# Power.net
KiCad netlist of a schematic drawn in Altium Designer
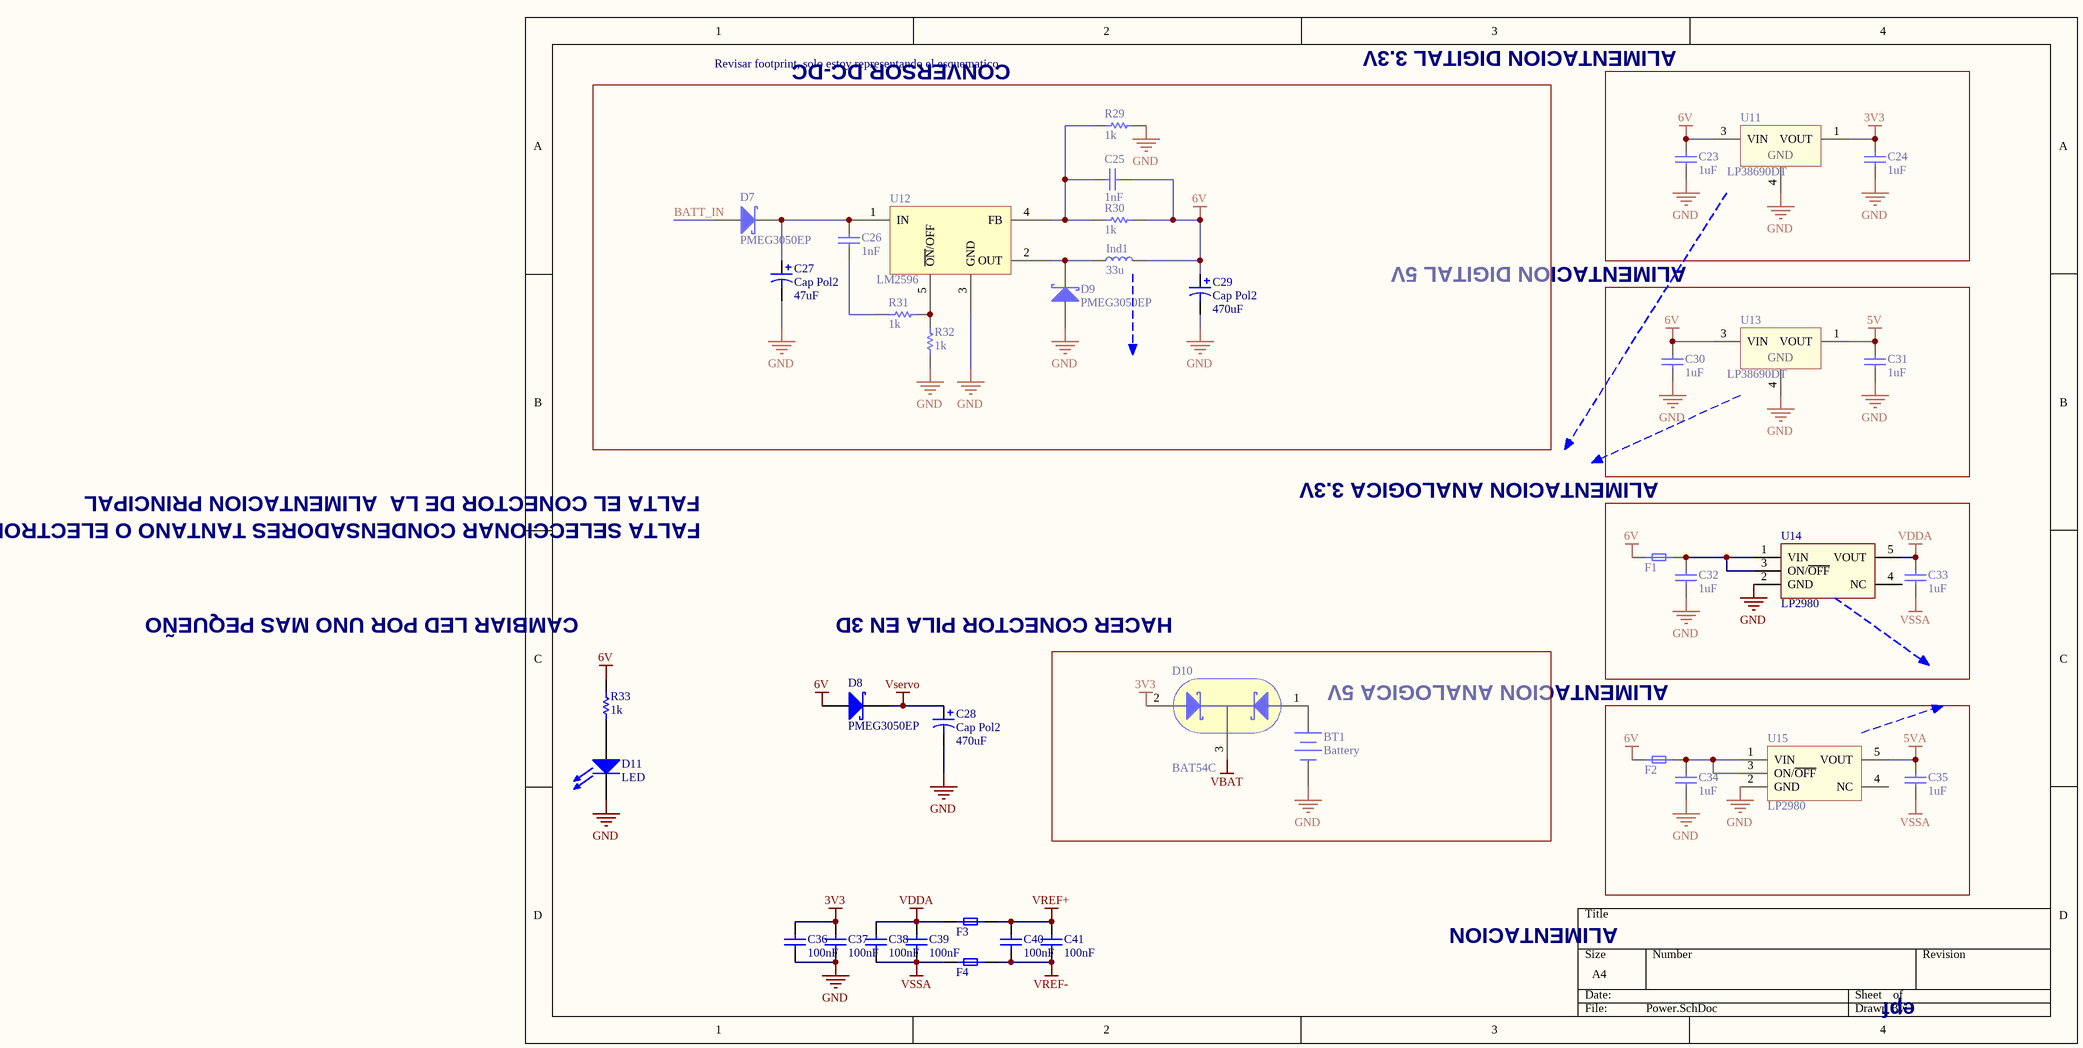
[diagram p0: Power.SchDoc]

(export (version "E")
  (design (tool "Eeschema 10.0.6"))
  (components
    (comp (ref "BT1")
      (value "Battery")
      (footprint "BC501SM")
      (description "Multicell Battery")
      (fields (field (name "PUBLISHER") "Altium Limited"))
      (libsource (lib "epf") (part "Battery"))
    )
    (comp (ref "C23")
      (value "1uF")
      (footprint "0805_CAP")
      (fields (field (name "Comment") "Capacitor"))
      (libsource (lib "epf") (part "Cap"))
    )
    (comp (ref "C24")
      (value "1uF")
      (footprint "0805_CAP")
      (fields (field (name "Comment") "Capacitor"))
      (libsource (lib "epf") (part "Cap"))
    )
    (comp (ref "C25")
      (value "1nF")
      (footprint "0805_CAP")
      (fields (field (name "Comment") "Capacitor"))
      (libsource (lib "epf") (part "Cap"))
    )
    (comp (ref "C26")
      (value "1nF")
      (footprint "0805_CAP")
      (fields (field (name "Comment") "Capacitor"))
      (libsource (lib "epf") (part "Cap"))
    )
    (comp (ref "C27")
      (value "Cap Pol2")
      (footprint "TC7360-2924")
      (description "Polarized Capacitor (Axial)")
      (fields (field (name "ALTIUM_VALUE") "47uF") (field (name "PUBLISHER") "Altium Limited"))
      (libsource (lib "epf") (part "Cap Pol2"))
    )
    (comp (ref "C28")
      (value "Cap Pol2")
      (footprint "TC7360-2924")
      (description "Polarized Capacitor (Axial)")
      (fields (field (name "ALTIUM_VALUE") "470uF") (field (name "PUBLISHER") "Altium Limited"))
      (libsource (lib "epf") (part "Cap Pol2"))
    )
    (comp (ref "C29")
      (value "Cap Pol2")
      (footprint "TC7360-2924")
      (description "Polarized Capacitor (Axial)")
      (fields (field (name "ALTIUM_VALUE") "470uF") (field (name "PUBLISHER") "Altium Limited"))
      (libsource (lib "epf") (part "Cap Pol2"))
    )
    (comp (ref "C30")
      (value "1uF")
      (footprint "0805_CAP")
      (fields (field (name "Comment") "Capacitor"))
      (libsource (lib "epf") (part "Cap"))
    )
    (comp (ref "C31")
      (value "1uF")
      (footprint "0805_CAP")
      (fields (field (name "Comment") "Capacitor"))
      (libsource (lib "epf") (part "Cap"))
    )
    (comp (ref "C32")
      (value "1uF")
      (footprint "CAP0402")
      (fields (field (name "Comment") "Capacitor"))
      (libsource (lib "epf") (part "Cap"))
    )
    (comp (ref "C33")
      (value "1uF")
      (footprint "CAP0402")
      (fields (field (name "Comment") "Capacitor"))
      (libsource (lib "epf") (part "Cap"))
    )
    (comp (ref "C34")
      (value "1uF")
      (footprint "CAP0402")
      (fields (field (name "Comment") "Capacitor"))
      (libsource (lib "epf") (part "Cap"))
    )
    (comp (ref "C35")
      (value "1uF")
      (footprint "CAP0402")
      (fields (field (name "Comment") "Capacitor"))
      (libsource (lib "epf") (part "Cap"))
    )
    (comp (ref "C36")
      (value "100nF")
      (footprint "CAP0402")
      (fields (field (name "Comment") "Capacitor"))
      (libsource (lib "epf") (part "Cap"))
    )
    (comp (ref "C37")
      (value "100nF")
      (footprint "CAP0402")
      (fields (field (name "Comment") "Capacitor"))
      (libsource (lib "epf") (part "Cap"))
    )
    (comp (ref "C38")
      (value "100nF")
      (footprint "CAP0402")
      (fields (field (name "Comment") "Capacitor"))
      (libsource (lib "epf") (part "Cap"))
    )
    (comp (ref "C39")
      (value "100nF")
      (footprint "CAP0402")
      (fields (field (name "Comment") "Capacitor"))
      (libsource (lib "epf") (part "Cap"))
    )
    (comp (ref "C40")
      (value "100nF")
      (footprint "CAP0402")
      (fields (field (name "Comment") "Capacitor"))
      (libsource (lib "epf") (part "Cap"))
    )
    (comp (ref "C41")
      (value "100nF")
      (footprint "CAP0402")
      (fields (field (name "Comment") "Capacitor"))
      (libsource (lib "epf") (part "Cap"))
    )
    (comp (ref "D7")
      (value "PMEG3050EP")
      (footprint "SOD128")
      (description "DIODO 5A DC-DC")
      (libsource (lib "epf") (part "PMEG3050EP"))
    )
    (comp (ref "D8")
      (value "PMEG3050EP")
      (footprint "SOD128")
      (description "DIODO 5A DC-DC")
      (libsource (lib "epf") (part "PMEG3050EP"))
    )
    (comp (ref "D9")
      (value "PMEG3050EP")
      (footprint "SOD128")
      (description "DIODO 5A DC-DC")
      (libsource (lib "epf") (part "PMEG3050EP"))
    )
    (comp (ref "D10")
      (value "BAT54C")
      (footprint "SOT23")
      (description "Single schottky")
      (libsource (lib "epf") (part "BAT54C"))
    )
    (comp (ref "D11") (value "LED") (footprint "PLCC-2Rojo") (libsource (lib "epf") (part "LED1")))
    (comp (ref "F1") (value "Ferrita") (footprint "IND0603") (libsource (lib "epf") (part "Ferrita")))
    (comp (ref "F2") (value "Ferrita") (footprint "IND0603") (libsource (lib "epf") (part "Ferrita")))
    (comp (ref "F3") (value "Ferrita") (footprint "IND0603") (libsource (lib "epf") (part "Ferrita")))
    (comp (ref "F4") (value "Ferrita") (footprint "IND0603") (libsource (lib "epf") (part "Ferrita")))
    (comp (ref "Ind1")
      (value "Ind2")
      (footprint "CDRH127")
      (fields (field (name "VALOR") "33u"))
      (libsource (lib "epf") (part "Ind2"))
    )
    (comp (ref "R29")
      (value "1k")
      (footprint "0805_RES")
      (fields (field (name "Comment") "Resistor"))
      (libsource (lib "epf") (part "Res"))
    )
    (comp (ref "R30")
      (value "1k")
      (footprint "0805_RES")
      (fields (field (name "Comment") "Resistor"))
      (libsource (lib "epf") (part "Res"))
    )
    (comp (ref "R31")
      (value "1k")
      (footprint "0805_RES")
      (fields (field (name "Comment") "Resistor"))
      (libsource (lib "epf") (part "Res"))
    )
    (comp (ref "R32")
      (value "1k")
      (footprint "0805_RES")
      (fields (field (name "Comment") "Resistor"))
      (libsource (lib "epf") (part "Res"))
    )
    (comp (ref "R33")
      (value "1k")
      (footprint "RES0402")
      (fields (field (name "Comment") "Resistor"))
      (libsource (lib "epf") (part "Res"))
    )
    (comp (ref "U11")
      (value "LP38690DT")
      (footprint "TO252-3N")
      (description "Current 1A")
      (libsource (lib "epf") (part "LP38690DT"))
    )
    (comp (ref "U12") (value "LM2596") (footprint "TO-263 - LM2596") (libsource (lib "epf") (part "LM2596")))
    (comp (ref "U13")
      (value "LP38690DT")
      (footprint "TO252-3N")
      (description "Current 1A")
      (libsource (lib "epf") (part "LP38690DT"))
    )
    (comp (ref "U14")
      (value "LP2980")
      (footprint "SOT23-5BN")
      (description "Current 50mA")
      (libsource (lib "epf") (part "LP2980"))
    )
    (comp (ref "U15")
      (value "LP2980")
      (footprint "SOT23-5BN")
      (description "Current 50mA")
      (libsource (lib "epf") (part "LP2980"))
    )
  )
  (nets
    (net (code "1") (name "/BATT_IN") (class "Default")
      (node (ref "D7") (pin "2") (pinfunction "A_2") (pintype "passive"))
    )
    (net (code "2") (name "3V3") (class "Default")
      (node (ref "C24") (pin "2") (pinfunction "2_2") (pintype "passive"))
      (node (ref "C36") (pin "2") (pinfunction "2_2") (pintype "passive"))
      (node (ref "C37") (pin "2") (pinfunction "2_2") (pintype "passive"))
      (node (ref "D10") (pin "2") (pinfunction "NC_2") (pintype "passive"))
      (node (ref "U11") (pin "1") (pinfunction "VOUT_1") (pintype "passive"))
    )
    (net (code "3") (name "5V") (class "Default")
      (node (ref "C31") (pin "2") (pinfunction "2_2") (pintype "passive"))
      (node (ref "U13") (pin "1") (pinfunction "VOUT_1") (pintype "passive"))
    )
    (net (code "4") (name "5VA") (class "Default")
      (node (ref "C35") (pin "2") (pinfunction "2_2") (pintype "passive"))
      (node (ref "U15") (pin "5") (pinfunction "VOUT_5") (pintype "passive"))
    )
    (net (code "5") (name "6V") (class "Default")
      (node (ref "C23") (pin "2") (pinfunction "2_2") (pintype "passive"))
      (node (ref "C25") (pin "1") (pinfunction "1_1") (pintype "passive"))
      (node (ref "C29") (pin "1") (pinfunction "1_1") (pintype "passive"))
      (node (ref "C30") (pin "2") (pinfunction "2_2") (pintype "passive"))
      (node (ref "D8") (pin "2") (pinfunction "A_2") (pintype "passive"))
      (node (ref "F1") (pin "1") (pinfunction "1_1") (pintype "passive"))
      (node (ref "F2") (pin "1") (pinfunction "1_1") (pintype "passive"))
      (node (ref "Ind1") (pin "2") (pinfunction "2_2") (pintype "passive"))
      (node (ref "R30") (pin "2") (pinfunction "2_2") (pintype "passive"))
      (node (ref "R33") (pin "1") (pinfunction "1_1") (pintype "passive"))
      (node (ref "U11") (pin "3") (pinfunction "VIN_3") (pintype "passive"))
      (node (ref "U13") (pin "3") (pinfunction "VIN_3") (pintype "passive"))
    )
    (net (code "6") (name "GND") (class "Default")
      (node (ref "BT1") (pin "2") (pinfunction "-_2") (pintype "passive"))
      (node (ref "C23") (pin "1") (pinfunction "1_1") (pintype "passive"))
      (node (ref "C24") (pin "1") (pinfunction "1_1") (pintype "passive"))
      (node (ref "C27") (pin "2") (pinfunction "2_2") (pintype "passive"))
      (node (ref "C28") (pin "2") (pinfunction "2_2") (pintype "passive"))
      (node (ref "C29") (pin "2") (pinfunction "2_2") (pintype "passive"))
      (node (ref "C30") (pin "1") (pinfunction "1_1") (pintype "passive"))
      (node (ref "C31") (pin "1") (pinfunction "1_1") (pintype "passive"))
      (node (ref "C32") (pin "1") (pinfunction "1_1") (pintype "passive"))
      (node (ref "C34") (pin "1") (pinfunction "1_1") (pintype "passive"))
      (node (ref "C36") (pin "1") (pinfunction "1_1") (pintype "passive"))
      (node (ref "C37") (pin "1") (pinfunction "1_1") (pintype "passive"))
      (node (ref "D11") (pin "2") (pinfunction "K_2") (pintype "passive"))
      (node (ref "D9") (pin "2") (pinfunction "A_2") (pintype "passive"))
      (node (ref "R29") (pin "2") (pinfunction "2_2") (pintype "passive"))
      (node (ref "R32") (pin "1") (pinfunction "1_1") (pintype "passive"))
      (node (ref "U11") (pin "4") (pinfunction "GND_4") (pintype "passive"))
      (node (ref "U12") (pin "3") (pinfunction "GND_3") (pintype "passive"))
      (node (ref "U13") (pin "4") (pinfunction "GND_4") (pintype "passive"))
      (node (ref "U14") (pin "2") (pinfunction "GND_2") (pintype "passive"))
      (node (ref "U15") (pin "2") (pinfunction "GND_2") (pintype "passive"))
    )
    (net (code "7") (name "Net-(BT1-+)") (class "Default")
      (node (ref "BT1") (pin "1") (pinfunction "+_1") (pintype "passive"))
      (node (ref "D10") (pin "1") (pinfunction "A_1") (pintype "passive"))
    )
    (net (code "8") (name "Net-(C26-Pad1)") (class "Default")
      (node (ref "C26") (pin "1") (pinfunction "1_1") (pintype "passive"))
      (node (ref "R31") (pin "1") (pinfunction "1_1") (pintype "passive"))
    )
    (net (code "9") (name "Net-(D7-K)") (class "Default")
      (node (ref "C26") (pin "2") (pinfunction "2_2") (pintype "passive"))
      (node (ref "C27") (pin "1") (pinfunction "1_1") (pintype "passive"))
      (node (ref "D7") (pin "1") (pinfunction "K_1") (pintype "passive"))
      (node (ref "U12") (pin "1") (pinfunction "IN_1") (pintype "passive"))
    )
    (net (code "10") (name "Net-(D9-K)") (class "Default")
      (node (ref "D9") (pin "1") (pinfunction "K_1") (pintype "passive"))
      (node (ref "Ind1") (pin "1") (pinfunction "1_1") (pintype "passive"))
      (node (ref "U12") (pin "2") (pinfunction "OUT_2") (pintype "passive"))
    )
    (net (code "11") (name "Net-(D11-A)") (class "Default")
      (node (ref "D11") (pin "1") (pinfunction "A_1") (pintype "passive"))
      (node (ref "R33") (pin "2") (pinfunction "2_2") (pintype "passive"))
    )
    (net (code "12") (name "Net-(U12-FB)") (class "Default")
      (node (ref "C25") (pin "2") (pinfunction "2_2") (pintype "passive"))
      (node (ref "R29") (pin "1") (pinfunction "1_1") (pintype "passive"))
      (node (ref "R30") (pin "1") (pinfunction "1_1") (pintype "passive"))
      (node (ref "U12") (pin "4") (pinfunction "FB_4") (pintype "passive"))
    )
    (net (code "13") (name "Net-(U12-~{ON}{slash}OFF)") (class "Default")
      (node (ref "R31") (pin "2") (pinfunction "2_2") (pintype "passive"))
      (node (ref "R32") (pin "2") (pinfunction "2_2") (pintype "passive"))
      (node (ref "U12") (pin "5") (pinfunction "~{ON}/OFF_5") (pintype "passive"))
    )
    (net (code "14") (name "Net-(U14-ON{slash}~{OFF})") (class "Default")
      (node (ref "C32") (pin "2") (pinfunction "2_2") (pintype "passive"))
      (node (ref "F1") (pin "2") (pinfunction "2_2") (pintype "passive"))
      (node (ref "U14") (pin "1") (pinfunction "VIN_1") (pintype "passive"))
      (node (ref "U14") (pin "3") (pinfunction "ON/~{OFF}_3") (pintype "passive"))
    )
    (net (code "15") (name "Net-(U15-ON{slash}~{OFF})") (class "Default")
      (node (ref "C34") (pin "2") (pinfunction "2_2") (pintype "passive"))
      (node (ref "F2") (pin "2") (pinfunction "2_2") (pintype "passive"))
      (node (ref "U15") (pin "1") (pinfunction "VIN_1") (pintype "passive"))
      (node (ref "U15") (pin "3") (pinfunction "ON/~{OFF}_3") (pintype "passive"))
    )
    (net (code "16") (name "VBAT") (class "Default")
      (node (ref "D10") (pin "3") (pinfunction "K_3") (pintype "passive"))
    )
    (net (code "17") (name "VDDA") (class "Default")
      (node (ref "C33") (pin "2") (pinfunction "2_2") (pintype "passive"))
      (node (ref "C38") (pin "2") (pinfunction "2_2") (pintype "passive"))
      (node (ref "C39") (pin "2") (pinfunction "2_2") (pintype "passive"))
      (node (ref "F3") (pin "1") (pinfunction "1_1") (pintype "passive"))
      (node (ref "U14") (pin "5") (pinfunction "VOUT_5") (pintype "passive"))
    )
    (net (code "18") (name "VREF+") (class "Default")
      (node (ref "C40") (pin "2") (pinfunction "2_2") (pintype "passive"))
      (node (ref "C41") (pin "2") (pinfunction "2_2") (pintype "passive"))
      (node (ref "F3") (pin "2") (pinfunction "2_2") (pintype "passive"))
    )
    (net (code "19") (name "VREF-") (class "Default")
      (node (ref "C40") (pin "1") (pinfunction "1_1") (pintype "passive"))
      (node (ref "C41") (pin "1") (pinfunction "1_1") (pintype "passive"))
      (node (ref "F4") (pin "2") (pinfunction "2_2") (pintype "passive"))
    )
    (net (code "20") (name "VSSA") (class "Default")
      (node (ref "C33") (pin "1") (pinfunction "1_1") (pintype "passive"))
      (node (ref "C35") (pin "1") (pinfunction "1_1") (pintype "passive"))
      (node (ref "C38") (pin "1") (pinfunction "1_1") (pintype "passive"))
      (node (ref "C39") (pin "1") (pinfunction "1_1") (pintype "passive"))
      (node (ref "F4") (pin "1") (pinfunction "1_1") (pintype "passive"))
    )
    (net (code "21") (name "Vservo") (class "Default")
      (node (ref "C28") (pin "1") (pinfunction "1_1") (pintype "passive"))
      (node (ref "D8") (pin "1") (pinfunction "K_1") (pintype "passive"))
    )
    (net (code "22") (name "unconnected-(U14-NC-Pad4)") (class "Default")
      (node (ref "U14") (pin "4") (pinfunction "NC_4") (pintype "passive"))
    )
    (net (code "23") (name "unconnected-(U15-NC-Pad4)") (class "Default")
      (node (ref "U15") (pin "4") (pinfunction "NC_4") (pintype "passive"))
    )
  )
)
